# Kello_Mechanical.net
KiCad netlist of a schematic drawn in Altium Designer
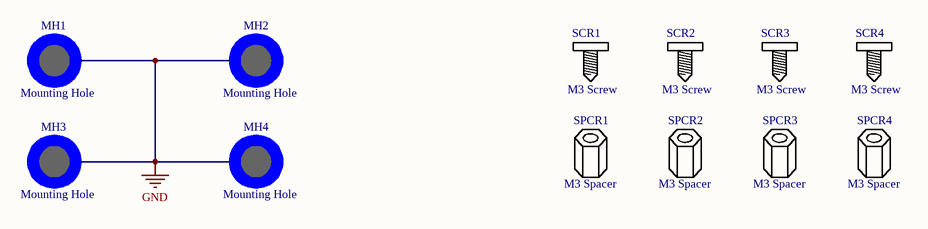
[diagram p0: Kello_Mechanical.SchDoc]

(export (version "E")
  (design (tool "Eeschema 10.0.6"))
  (components
    (comp (ref "MH1")
      (value "Mounting Hole")
      (footprint "MH-M3_Copper")
      (description "M3 mounting hole")
      (libsource (lib "PCB") (part "MH"))
    )
    (comp (ref "MH2")
      (value "Mounting Hole")
      (footprint "MH-M3_Copper")
      (description "M3 mounting hole")
      (libsource (lib "PCB") (part "MH"))
    )
    (comp (ref "MH3")
      (value "Mounting Hole")
      (footprint "MH-M3_Copper")
      (description "M3 mounting hole")
      (libsource (lib "PCB") (part "MH"))
    )
    (comp (ref "MH4")
      (value "Mounting Hole")
      (footprint "MH-M3_Copper")
      (description "M3 mounting hole")
      (libsource (lib "PCB") (part "MH"))
    )
    (comp (ref "SCR1") (value "M3 Screw") (libsource (lib "Mechanical") (part "SCREW")))
    (comp (ref "SCR2") (value "M3 Screw") (libsource (lib "Mechanical") (part "SCREW")))
    (comp (ref "SCR3") (value "M3 Screw") (libsource (lib "Mechanical") (part "SCREW")))
    (comp (ref "SCR4") (value "M3 Screw") (libsource (lib "Mechanical") (part "SCREW")))
    (comp (ref "SPCR1") (value "M3 Spacer") (libsource (lib "Mechanical") (part "SPCR")))
    (comp (ref "SPCR2") (value "M3 Spacer") (libsource (lib "Mechanical") (part "SPCR")))
    (comp (ref "SPCR3") (value "M3 Spacer") (libsource (lib "Mechanical") (part "SPCR")))
    (comp (ref "SPCR4") (value "M3 Spacer") (libsource (lib "Mechanical") (part "SPCR")))
  )
  (nets
    (net (code "1") (name "GND") (class "Default")
      (node (ref "MH1") (pin "MH") (pinfunction "MH_MH") (pintype "passive"))
      (node (ref "MH2") (pin "MH") (pinfunction "MH_MH") (pintype "passive"))
      (node (ref "MH3") (pin "MH") (pinfunction "MH_MH") (pintype "passive"))
      (node (ref "MH4") (pin "MH") (pinfunction "MH_MH") (pintype "passive"))
    )
  )
)
